# MCU.net
KiCad netlist of a schematic drawn in Altium Designer
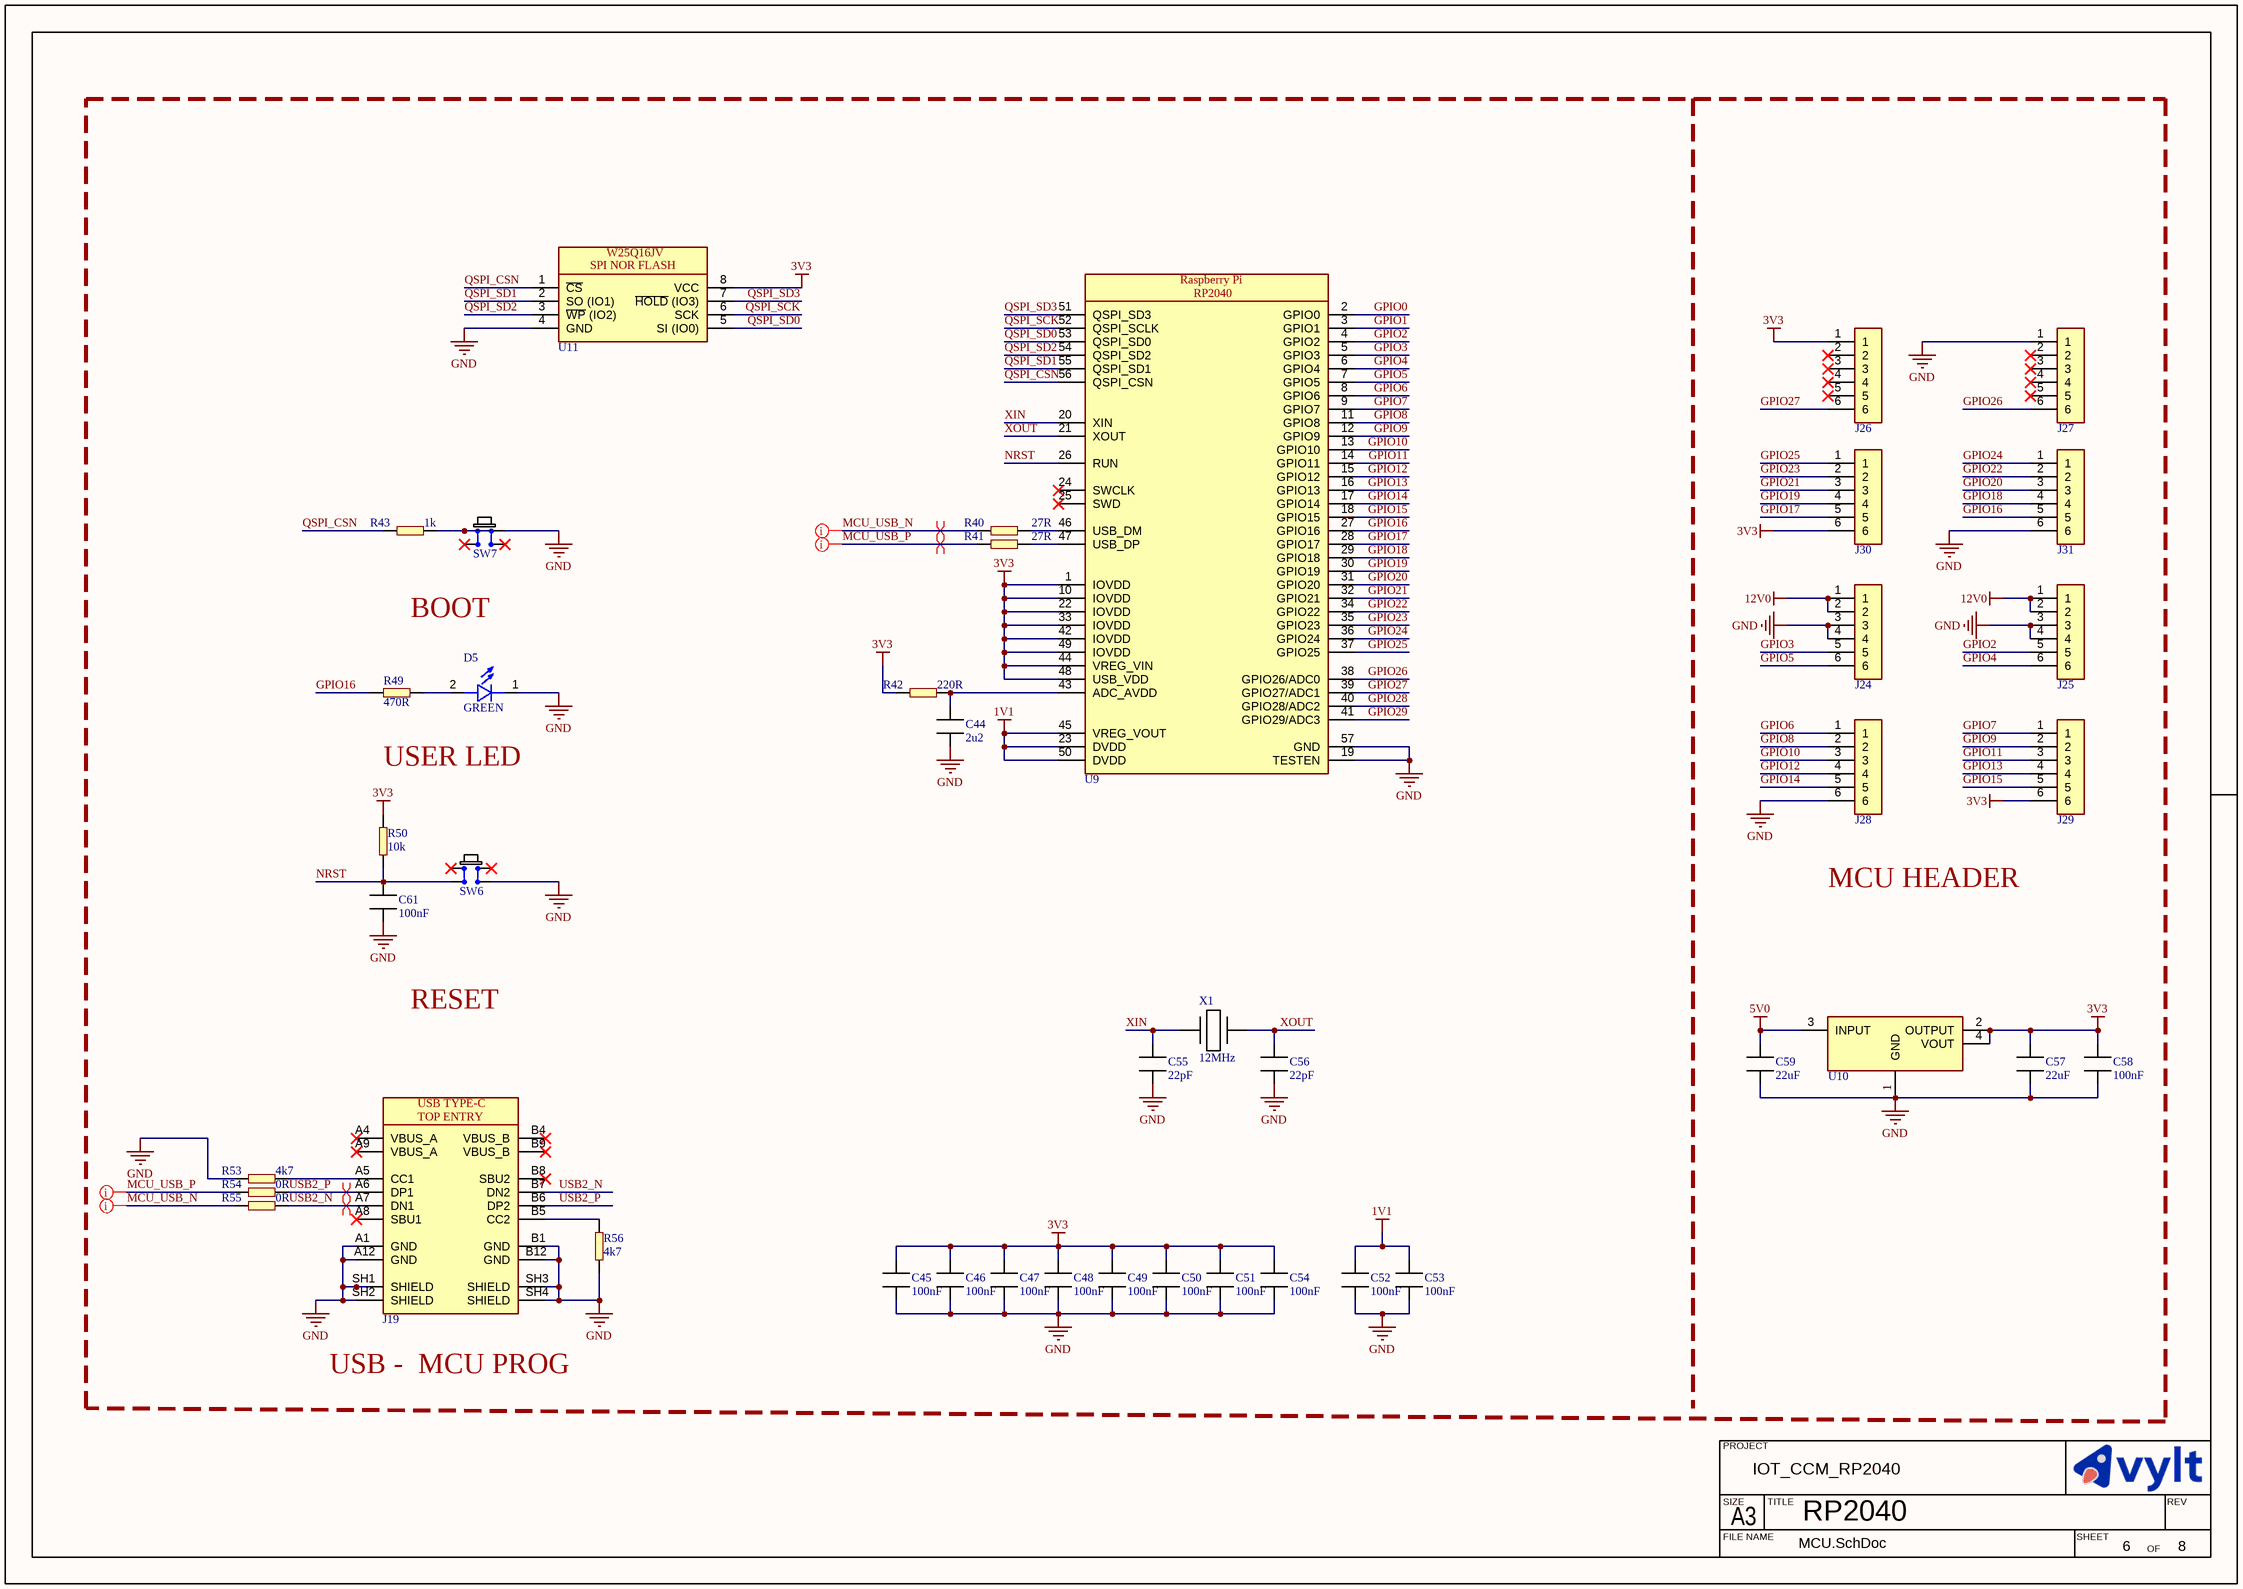
[diagram p0: MCU.SchDoc]

(export (version "E")
  (design (tool "Eeschema 10.0.6"))
  (components
    (comp (ref "C44")
      (value "2u2")
      (footprint "CAPC2012X13L")
      (description "Chip Capacitor, 2-Leads, Body 2.00x1.25mm, IPC High Density")
      (fields (field (name "Comment") "MLCC_0805"))
      (libsource (lib "Capacitor") (part "MLCC_0805"))
    )
    (comp (ref "C45")
      (value "100nF")
      (footprint "CAPC2012X13L")
      (description "Chip Capacitor, 2-Leads, Body 2.00x1.25mm, IPC High Density")
      (fields (field (name "Comment") "MLCC_0805"))
      (libsource (lib "Capacitor") (part "MLCC_0805"))
    )
    (comp (ref "C46")
      (value "100nF")
      (footprint "CAPC2012X13L")
      (description "Chip Capacitor, 2-Leads, Body 2.00x1.25mm, IPC High Density")
      (fields (field (name "Comment") "MLCC_0805"))
      (libsource (lib "Capacitor") (part "MLCC_0805"))
    )
    (comp (ref "C47")
      (value "100nF")
      (footprint "CAPC2012X13L")
      (description "Chip Capacitor, 2-Leads, Body 2.00x1.25mm, IPC High Density")
      (fields (field (name "Comment") "MLCC_0805"))
      (libsource (lib "Capacitor") (part "MLCC_0805"))
    )
    (comp (ref "C48")
      (value "100nF")
      (footprint "CAPC2012X13L")
      (description "Chip Capacitor, 2-Leads, Body 2.00x1.25mm, IPC High Density")
      (fields (field (name "Comment") "MLCC_0805"))
      (libsource (lib "Capacitor") (part "MLCC_0805"))
    )
    (comp (ref "C49")
      (value "100nF")
      (footprint "CAPC2012X13L")
      (description "Chip Capacitor, 2-Leads, Body 2.00x1.25mm, IPC High Density")
      (fields (field (name "Comment") "MLCC_0805"))
      (libsource (lib "Capacitor") (part "MLCC_0805"))
    )
    (comp (ref "C50")
      (value "100nF")
      (footprint "CAPC2012X13L")
      (description "Chip Capacitor, 2-Leads, Body 2.00x1.25mm, IPC High Density")
      (fields (field (name "Comment") "MLCC_0805"))
      (libsource (lib "Capacitor") (part "MLCC_0805"))
    )
    (comp (ref "C51")
      (value "100nF")
      (footprint "CAPC2012X13L")
      (description "Chip Capacitor, 2-Leads, Body 2.00x1.25mm, IPC High Density")
      (fields (field (name "Comment") "MLCC_0805"))
      (libsource (lib "Capacitor") (part "MLCC_0805"))
    )
    (comp (ref "C52")
      (value "100nF")
      (footprint "CAPC2012X13L")
      (description "Chip Capacitor, 2-Leads, Body 2.00x1.25mm, IPC High Density")
      (fields (field (name "Comment") "MLCC_0805"))
      (libsource (lib "Capacitor") (part "MLCC_0805"))
    )
    (comp (ref "C53")
      (value "100nF")
      (footprint "CAPC2012X13L")
      (description "Chip Capacitor, 2-Leads, Body 2.00x1.25mm, IPC High Density")
      (fields (field (name "Comment") "MLCC_0805"))
      (libsource (lib "Capacitor") (part "MLCC_0805"))
    )
    (comp (ref "C54")
      (value "100nF")
      (footprint "CAPC2012X13L")
      (description "Chip Capacitor, 2-Leads, Body 2.00x1.25mm, IPC High Density")
      (fields (field (name "Comment") "MLCC_0805"))
      (libsource (lib "Capacitor") (part "MLCC_0805"))
    )
    (comp (ref "C55")
      (value "22pF")
      (footprint "CAPC2012X13L")
      (description "Chip Capacitor, 2-Leads, Body 2.00x1.25mm, IPC High Density")
      (fields (field (name "Comment") "MLCC_0805"))
      (libsource (lib "Capacitor") (part "MLCC_0805"))
    )
    (comp (ref "C56")
      (value "22pF")
      (footprint "CAPC2012X13L")
      (description "Chip Capacitor, 2-Leads, Body 2.00x1.25mm, IPC High Density")
      (fields (field (name "Comment") "MLCC_0805"))
      (libsource (lib "Capacitor") (part "MLCC_0805"))
    )
    (comp (ref "C57")
      (value "22uF")
      (footprint "CAPC2012X13L")
      (description "Chip Capacitor, 2-Leads, Body 2.00x1.25mm, IPC High Density")
      (fields (field (name "Comment") "MLCC_0805"))
      (libsource (lib "Capacitor") (part "MLCC_0805"))
    )
    (comp (ref "C58")
      (value "100nF")
      (footprint "CAPC2012X13L")
      (description "Chip Capacitor, 2-Leads, Body 2.00x1.25mm, IPC High Density")
      (fields (field (name "Comment") "MLCC_0805"))
      (libsource (lib "Capacitor") (part "MLCC_0805"))
    )
    (comp (ref "C59")
      (value "22uF")
      (footprint "CAPC2012X13L")
      (description "Chip Capacitor, 2-Leads, Body 2.00x1.25mm, IPC High Density")
      (fields (field (name "Comment") "MLCC_0805"))
      (libsource (lib "Capacitor") (part "MLCC_0805"))
    )
    (comp (ref "C61")
      (value "100nF")
      (footprint "CAPC2012X13L")
      (description "Chip Capacitor, 2-Leads, Body 2.00x1.25mm, IPC High Density")
      (fields (field (name "Comment") "MLCC_0805"))
      (libsource (lib "Capacitor") (part "MLCC_0805"))
    )
    (comp (ref "D5")
      (value "GREEN")
      (footprint "LED_1206")
      (description "LED CLEAR 1206 SMD")
      (fields (field (name "Comment") "LED_1206"))
      (libsource (lib "LED") (part "LED_1206"))
    )
    (comp (ref "J19")
      (value "GSB1CA11101DSHR")
      (footprint "GSB1CA11101DSHR")
      (libsource (lib "Connectors") (part "GSB1CA11101DSHR"))
    )
    (comp (ref "J24")
      (value "ERP_148-2")
      (footprint "6PX1R_F")
      (description "6PX1R Female Header")
      (libsource (lib "PinHeader") (part "6PX1R_F"))
    )
    (comp (ref "J25")
      (value "ERP_148-2")
      (footprint "6PX1R_F")
      (description "6PX1R Female Header")
      (libsource (lib "PinHeader") (part "6PX1R_F"))
    )
    (comp (ref "J26")
      (value "ERP_148-2")
      (footprint "6PX1R_F")
      (description "6PX1R Female Header")
      (libsource (lib "PinHeader") (part "6PX1R_F"))
    )
    (comp (ref "J27")
      (value "ERP_148-2")
      (footprint "6PX1R_F")
      (description "6PX1R Female Header")
      (libsource (lib "PinHeader") (part "6PX1R_F"))
    )
    (comp (ref "J28")
      (value "ERP_148-2")
      (footprint "6PX1R_F")
      (description "6PX1R Female Header")
      (libsource (lib "PinHeader") (part "6PX1R_F"))
    )
    (comp (ref "J29")
      (value "ERP_148-2")
      (footprint "6PX1R_F")
      (description "6PX1R Female Header")
      (libsource (lib "PinHeader") (part "6PX1R_F"))
    )
    (comp (ref "J30")
      (value "ERP_148-2")
      (footprint "6PX1R_F")
      (description "6PX1R Female Header")
      (libsource (lib "PinHeader") (part "6PX1R_F"))
    )
    (comp (ref "J31")
      (value "ERP_148-2")
      (footprint "6PX1R_F")
      (description "6PX1R Female Header")
      (libsource (lib "PinHeader") (part "6PX1R_F"))
    )
    (comp (ref "R40")
      (value "27R")
      (footprint "RES_0603")
      (description "RES_0603")
      (fields (field (name "Comment") "ERP_101-1"))
      (libsource (lib "") (part "RES_0603_1"))
    )
    (comp (ref "R41")
      (value "27R")
      (footprint "RES_0603")
      (description "RES_0603")
      (fields (field (name "Comment") "ERP_101-1"))
      (libsource (lib "") (part "RES_0603_1"))
    )
    (comp (ref "R42")
      (value "220R")
      (footprint "RES_0603")
      (description "RES_0603")
      (fields (field (name "Comment") "ERP_101-1"))
      (libsource (lib "") (part "RES_0603_1"))
    )
    (comp (ref "R43")
      (value "1k")
      (footprint "RES_0603")
      (description "RES_0603")
      (fields (field (name "Comment") "ERP_101-1"))
      (libsource (lib "") (part "RES_0603_1"))
    )
    (comp (ref "R49")
      (value "470R")
      (footprint "RES_0603")
      (description "RES_0603")
      (fields (field (name "Comment") "ERP_101-1"))
      (libsource (lib "") (part "RES_0603_1"))
    )
    (comp (ref "R50")
      (value "10k")
      (footprint "RES_0603")
      (description "RES_0603")
      (fields (field (name "Comment") "ERP_101-1"))
      (libsource (lib "Resistor") (part "RES_0603"))
    )
    (comp (ref "R53")
      (value "4k7")
      (footprint "RES_0603")
      (description "RES_0603")
      (fields (field (name "Comment") "ERP_101-1"))
      (libsource (lib "") (part "RES_0603_1"))
    )
    (comp (ref "R54")
      (value "0R")
      (footprint "RES_0603")
      (description "RES_0603")
      (fields (field (name "Comment") "ERP_101-1"))
      (libsource (lib "") (part "RES_0603_1"))
    )
    (comp (ref "R55")
      (value "0R")
      (footprint "RES_0603")
      (description "RES_0603")
      (fields (field (name "Comment") "ERP_101-1"))
      (libsource (lib "") (part "RES_0603_1"))
    )
    (comp (ref "R56")
      (value "4k7")
      (footprint "RES_0603")
      (description "RES_0603")
      (fields (field (name "Comment") "ERP_101-1"))
      (libsource (lib "") (part "RES_0603_2"))
    )
    (comp (ref "SW6")
      (value "Generic6X6")
      (footprint "Generic6X6")
      (description "Tactile Switch SPST-NO Top Actuated Surface Mount")
      (libsource (lib "Switch") (part "Generic6X6"))
    )
    (comp (ref "SW7")
      (value "Generic6X6")
      (footprint "Generic6X6")
      (description "Tactile Switch SPST-NO Top Actuated Surface Mount")
      (libsource (lib "Switch") (part "Generic6X6"))
    )
    (comp (ref "U9")
      (value "RP2040")
      (footprint "QFN40P700X700X90-57N")
      (description "ARM® Cortex®-M0+ - Microcontroller IC 32-Bit Dual-Core 133MHz External Program Memory 56-QFN (7x7)")
      (libsource (lib "MCU") (part "RP2040"))
    )
    (comp (ref "U10")
      (value "ERP_123-1")
      (footprint "AMS1117_SOT223")
      (description "AMS1117 LDO")
      (libsource (lib "VoltageRegulator") (part "AMS1117_SOT223"))
    )
    (comp (ref "U11")
      (value "W25Q16JV")
      (footprint "SOIC127P600X175-8M")
      (description "FLASH - NOR Memory IC SPI - Quad I/O 133 MHz 8-SOIC")
      (libsource (lib "FLASH") (part "W25Q16JV"))
    )
    (comp (ref "X1")
      (value "12MHz")
      (footprint "X5032")
      (description "CRYSTAL X5032 2 Pin")
      (fields (field (name "Comment") "X5032"))
      (libsource (lib "Crystal") (part "X5032"))
    )
  )
  (nets
    (net (code "1") (name "/GPIO0") (class "Default")
      (node (ref "U9") (pin "2") (pinfunction "GPIO0_2") (pintype "passive"))
    )
    (net (code "2") (name "/GPIO1") (class "Default")
      (node (ref "U9") (pin "3") (pinfunction "GPIO1_3") (pintype "passive"))
    )
    (net (code "3") (name "/GPIO2") (class "Default")
      (node (ref "J25") (pin "5") (pinfunction "5_5") (pintype "passive"))
      (node (ref "U9") (pin "4") (pinfunction "GPIO2_4") (pintype "passive"))
    )
    (net (code "4") (name "/GPIO3") (class "Default")
      (node (ref "J24") (pin "5") (pinfunction "5_5") (pintype "passive"))
      (node (ref "U9") (pin "5") (pinfunction "GPIO3_5") (pintype "passive"))
    )
    (net (code "5") (name "/GPIO4") (class "Default")
      (node (ref "J25") (pin "6") (pinfunction "6_6") (pintype "passive"))
      (node (ref "U9") (pin "6") (pinfunction "GPIO4_6") (pintype "passive"))
    )
    (net (code "6") (name "/GPIO5") (class "Default")
      (node (ref "J24") (pin "6") (pinfunction "6_6") (pintype "passive"))
      (node (ref "U9") (pin "7") (pinfunction "GPIO5_7") (pintype "passive"))
    )
    (net (code "7") (name "/GPIO6") (class "Default")
      (node (ref "J28") (pin "1") (pinfunction "1_1") (pintype "passive"))
      (node (ref "U9") (pin "8") (pinfunction "GPIO6_8") (pintype "passive"))
    )
    (net (code "8") (name "/GPIO7") (class "Default")
      (node (ref "J29") (pin "1") (pinfunction "1_1") (pintype "passive"))
      (node (ref "U9") (pin "9") (pinfunction "GPIO7_9") (pintype "passive"))
    )
    (net (code "9") (name "/GPIO8") (class "Default")
      (node (ref "J28") (pin "2") (pinfunction "2_2") (pintype "passive"))
      (node (ref "U9") (pin "11") (pinfunction "GPIO8_11") (pintype "passive"))
    )
    (net (code "10") (name "/GPIO9") (class "Default")
      (node (ref "J29") (pin "2") (pinfunction "2_2") (pintype "passive"))
      (node (ref "U9") (pin "12") (pinfunction "GPIO9_12") (pintype "passive"))
    )
    (net (code "11") (name "/GPIO10") (class "Default")
      (node (ref "J28") (pin "3") (pinfunction "3_3") (pintype "passive"))
      (node (ref "U9") (pin "13") (pinfunction "GPIO10_13") (pintype "passive"))
    )
    (net (code "12") (name "/GPIO11") (class "Default")
      (node (ref "J29") (pin "3") (pinfunction "3_3") (pintype "passive"))
      (node (ref "U9") (pin "14") (pinfunction "GPIO11_14") (pintype "passive"))
    )
    (net (code "13") (name "/GPIO12") (class "Default")
      (node (ref "J28") (pin "4") (pinfunction "4_4") (pintype "passive"))
      (node (ref "U9") (pin "15") (pinfunction "GPIO12_15") (pintype "passive"))
    )
    (net (code "14") (name "/GPIO13") (class "Default")
      (node (ref "J29") (pin "4") (pinfunction "4_4") (pintype "passive"))
      (node (ref "U9") (pin "16") (pinfunction "GPIO13_16") (pintype "passive"))
    )
    (net (code "15") (name "/GPIO14") (class "Default")
      (node (ref "J28") (pin "5") (pinfunction "5_5") (pintype "passive"))
      (node (ref "U9") (pin "17") (pinfunction "GPIO14_17") (pintype "passive"))
    )
    (net (code "16") (name "/GPIO15") (class "Default")
      (node (ref "J29") (pin "5") (pinfunction "5_5") (pintype "passive"))
      (node (ref "U9") (pin "18") (pinfunction "GPIO15_18") (pintype "passive"))
    )
    (net (code "17") (name "/GPIO16") (class "Default")
      (node (ref "J31") (pin "5") (pinfunction "5_5") (pintype "passive"))
      (node (ref "R49") (pin "2") (pinfunction "2_2") (pintype "passive"))
      (node (ref "U9") (pin "27") (pinfunction "GPIO16_27") (pintype "passive"))
    )
    (net (code "18") (name "/GPIO17") (class "Default")
      (node (ref "J30") (pin "5") (pinfunction "5_5") (pintype "passive"))
      (node (ref "U9") (pin "28") (pinfunction "GPIO17_28") (pintype "passive"))
    )
    (net (code "19") (name "/GPIO18") (class "Default")
      (node (ref "J31") (pin "4") (pinfunction "4_4") (pintype "passive"))
      (node (ref "U9") (pin "29") (pinfunction "GPIO18_29") (pintype "passive"))
    )
    (net (code "20") (name "/GPIO19") (class "Default")
      (node (ref "J30") (pin "4") (pinfunction "4_4") (pintype "passive"))
      (node (ref "U9") (pin "30") (pinfunction "GPIO19_30") (pintype "passive"))
    )
    (net (code "21") (name "/GPIO20") (class "Default")
      (node (ref "J31") (pin "3") (pinfunction "3_3") (pintype "passive"))
      (node (ref "U9") (pin "31") (pinfunction "GPIO20_31") (pintype "passive"))
    )
    (net (code "22") (name "/GPIO21") (class "Default")
      (node (ref "J30") (pin "3") (pinfunction "3_3") (pintype "passive"))
      (node (ref "U9") (pin "32") (pinfunction "GPIO21_32") (pintype "passive"))
    )
    (net (code "23") (name "/GPIO22") (class "Default")
      (node (ref "J31") (pin "2") (pinfunction "2_2") (pintype "passive"))
      (node (ref "U9") (pin "34") (pinfunction "GPIO22_34") (pintype "passive"))
    )
    (net (code "24") (name "/GPIO23") (class "Default")
      (node (ref "J30") (pin "2") (pinfunction "2_2") (pintype "passive"))
      (node (ref "U9") (pin "35") (pinfunction "GPIO23_35") (pintype "passive"))
    )
    (net (code "25") (name "/GPIO24") (class "Default")
      (node (ref "J31") (pin "1") (pinfunction "1_1") (pintype "passive"))
      (node (ref "U9") (pin "36") (pinfunction "GPIO24_36") (pintype "passive"))
    )
    (net (code "26") (name "/GPIO25") (class "Default")
      (node (ref "J30") (pin "1") (pinfunction "1_1") (pintype "passive"))
      (node (ref "U9") (pin "37") (pinfunction "GPIO25_37") (pintype "passive"))
    )
    (net (code "27") (name "/GPIO26") (class "Default")
      (node (ref "J27") (pin "6") (pinfunction "6_6") (pintype "passive"))
      (node (ref "U9") (pin "38") (pinfunction "GPIO26/ADC0_38") (pintype "passive"))
    )
    (net (code "28") (name "/GPIO27") (class "Default")
      (node (ref "J26") (pin "6") (pinfunction "6_6") (pintype "passive"))
      (node (ref "U9") (pin "39") (pinfunction "GPIO27/ADC1_39") (pintype "passive"))
    )
    (net (code "29") (name "/GPIO28") (class "Default")
      (node (ref "U9") (pin "40") (pinfunction "GPIO28/ADC2_40") (pintype "passive"))
    )
    (net (code "30") (name "/GPIO29") (class "Default")
      (node (ref "U9") (pin "41") (pinfunction "GPIO29/ADC3_41") (pintype "passive"))
    )
    (net (code "31") (name "/MCU_USB_N") (class "Default")
      (node (ref "R40") (pin "2") (pinfunction "2_2") (pintype "passive"))
      (node (ref "R55") (pin "2") (pinfunction "2_2") (pintype "passive"))
    )
    (net (code "32") (name "/MCU_USB_P") (class "Default")
      (node (ref "R41") (pin "2") (pinfunction "2_2") (pintype "passive"))
      (node (ref "R54") (pin "2") (pinfunction "2_2") (pintype "passive"))
    )
    (net (code "33") (name "/NRST") (class "Default")
      (node (ref "C61") (pin "1") (pinfunction "1_1") (pintype "passive"))
      (node (ref "R50") (pin "1") (pinfunction "1_1") (pintype "passive"))
      (node (ref "SW6") (pin "2") (pinfunction "NO_2") (pintype "passive"))
      (node (ref "U9") (pin "26") (pinfunction "RUN_26") (pintype "passive"))
    )
    (net (code "34") (name "/QSPI_CSN") (class "Default")
      (node (ref "R43") (pin "2") (pinfunction "2_2") (pintype "passive"))
      (node (ref "U11") (pin "1") (pinfunction "~{CS}_1") (pintype "passive"))
      (node (ref "U9") (pin "56") (pinfunction "QSPI_CSN_56") (pintype "passive"))
    )
    (net (code "35") (name "/QSPI_SCK") (class "Default")
      (node (ref "U11") (pin "6") (pinfunction "SCK_6") (pintype "passive"))
      (node (ref "U9") (pin "52") (pinfunction "QSPI_SCLK_52") (pintype "passive"))
    )
    (net (code "36") (name "/QSPI_SD0") (class "Default")
      (node (ref "U11") (pin "5") (pinfunction "SI_(IO0)_5") (pintype "passive"))
      (node (ref "U9") (pin "53") (pinfunction "QSPI_SD0_53") (pintype "passive"))
    )
    (net (code "37") (name "/QSPI_SD1") (class "Default")
      (node (ref "U11") (pin "2") (pinfunction "SO_(IO1)_2") (pintype "passive"))
      (node (ref "U9") (pin "55") (pinfunction "QSPI_SD1_55") (pintype "passive"))
    )
    (net (code "38") (name "/QSPI_SD2") (class "Default")
      (node (ref "U11") (pin "3") (pinfunction "~{WP}_(IO2)_3") (pintype "passive"))
      (node (ref "U9") (pin "54") (pinfunction "QSPI_SD2_54") (pintype "passive"))
    )
    (net (code "39") (name "/QSPI_SD3") (class "Default")
      (node (ref "U11") (pin "7") (pinfunction "~{HOLD}_(IO3)_7") (pintype "passive"))
      (node (ref "U9") (pin "51") (pinfunction "QSPI_SD3_51") (pintype "passive"))
    )
    (net (code "40") (name "/USB2_N") (class "Default")
      (node (ref "J19") (pin "A7") (pinfunction "DN1_A7") (pintype "passive"))
      (node (ref "J19") (pin "B7") (pinfunction "DN2_B7") (pintype "passive"))
      (node (ref "R55") (pin "1") (pinfunction "1_1") (pintype "passive"))
    )
    (net (code "41") (name "/USB2_P") (class "Default")
      (node (ref "J19") (pin "A6") (pinfunction "DP1_A6") (pintype "passive"))
      (node (ref "J19") (pin "B6") (pinfunction "DP2_B6") (pintype "passive"))
      (node (ref "R54") (pin "1") (pinfunction "1_1") (pintype "passive"))
    )
    (net (code "42") (name "/XIN") (class "Default")
      (node (ref "C55") (pin "1") (pinfunction "1_1") (pintype "passive"))
      (node (ref "U9") (pin "20") (pinfunction "XIN_20") (pintype "passive"))
      (node (ref "X1") (pin "1") (pinfunction "1_1") (pintype "passive"))
    )
    (net (code "43") (name "/XOUT") (class "Default")
      (node (ref "C56") (pin "1") (pinfunction "1_1") (pintype "passive"))
      (node (ref "U9") (pin "21") (pinfunction "XOUT_21") (pintype "passive"))
      (node (ref "X1") (pin "2") (pinfunction "2_2") (pintype "passive"))
    )
    (net (code "44") (name "1V1") (class "Default")
      (node (ref "C52") (pin "1") (pinfunction "1_1") (pintype "passive"))
      (node (ref "C53") (pin "1") (pinfunction "1_1") (pintype "passive"))
      (node (ref "U9") (pin "23") (pinfunction "DVDD_23") (pintype "passive"))
      (node (ref "U9") (pin "45") (pinfunction "VREG_VOUT_45") (pintype "passive"))
      (node (ref "U9") (pin "50") (pinfunction "DVDD_50") (pintype "passive"))
    )
    (net (code "45") (name "3V3") (class "Default")
      (node (ref "C45") (pin "1") (pinfunction "1_1") (pintype "passive"))
      (node (ref "C46") (pin "1") (pinfunction "1_1") (pintype "passive"))
      (node (ref "C47") (pin "1") (pinfunction "1_1") (pintype "passive"))
      (node (ref "C48") (pin "1") (pinfunction "1_1") (pintype "passive"))
      (node (ref "C49") (pin "1") (pinfunction "1_1") (pintype "passive"))
      (node (ref "C50") (pin "1") (pinfunction "1_1") (pintype "passive"))
      (node (ref "C51") (pin "1") (pinfunction "1_1") (pintype "passive"))
      (node (ref "C54") (pin "1") (pinfunction "1_1") (pintype "passive"))
      (node (ref "C57") (pin "1") (pinfunction "1_1") (pintype "passive"))
      (node (ref "C58") (pin "1") (pinfunction "1_1") (pintype "passive"))
      (node (ref "J26") (pin "1") (pinfunction "1_1") (pintype "passive"))
      (node (ref "J29") (pin "6") (pinfunction "6_6") (pintype "passive"))
      (node (ref "J30") (pin "6") (pinfunction "6_6") (pintype "passive"))
      (node (ref "R42") (pin "2") (pinfunction "2_2") (pintype "passive"))
      (node (ref "R50") (pin "2") (pinfunction "2_2") (pintype "passive"))
      (node (ref "U10") (pin "2") (pinfunction "OUTPUT_2") (pintype "passive"))
      (node (ref "U10") (pin "4") (pinfunction "VOUT_4") (pintype "passive"))
      (node (ref "U11") (pin "8") (pinfunction "VCC_8") (pintype "passive"))
      (node (ref "U9") (pin "1") (pinfunction "IOVDD_1") (pintype "passive"))
      (node (ref "U9") (pin "10") (pinfunction "IOVDD_10") (pintype "passive"))
      (node (ref "U9") (pin "22") (pinfunction "IOVDD_22") (pintype "passive"))
      (node (ref "U9") (pin "33") (pinfunction "IOVDD_33") (pintype "passive"))
      (node (ref "U9") (pin "42") (pinfunction "IOVDD_42") (pintype "passive"))
      (node (ref "U9") (pin "44") (pinfunction "VREG_VIN_44") (pintype "passive"))
      (node (ref "U9") (pin "48") (pinfunction "USB_VDD_48") (pintype "passive"))
      (node (ref "U9") (pin "49") (pinfunction "IOVDD_49") (pintype "passive"))
    )
    (net (code "46") (name "5V0") (class "Default")
      (node (ref "C59") (pin "1") (pinfunction "1_1") (pintype "passive"))
      (node (ref "U10") (pin "3") (pinfunction "INPUT_3") (pintype "passive"))
    )
    (net (code "47") (name "12V0") (class "Default")
      (node (ref "J24") (pin "1") (pinfunction "1_1") (pintype "passive"))
      (node (ref "J24") (pin "2") (pinfunction "2_2") (pintype "passive"))
      (node (ref "J25") (pin "1") (pinfunction "1_1") (pintype "passive"))
      (node (ref "J25") (pin "2") (pinfunction "2_2") (pintype "passive"))
    )
    (net (code "48") (name "GND") (class "Default")
      (node (ref "C44") (pin "2") (pinfunction "2_2") (pintype "passive"))
      (node (ref "C45") (pin "2") (pinfunction "2_2") (pintype "passive"))
      (node (ref "C46") (pin "2") (pinfunction "2_2") (pintype "passive"))
      (node (ref "C47") (pin "2") (pinfunction "2_2") (pintype "passive"))
      (node (ref "C48") (pin "2") (pinfunction "2_2") (pintype "passive"))
      (node (ref "C49") (pin "2") (pinfunction "2_2") (pintype "passive"))
      (node (ref "C50") (pin "2") (pinfunction "2_2") (pintype "passive"))
      (node (ref "C51") (pin "2") (pinfunction "2_2") (pintype "passive"))
      (node (ref "C52") (pin "2") (pinfunction "2_2") (pintype "passive"))
      (node (ref "C53") (pin "2") (pinfunction "2_2") (pintype "passive"))
      (node (ref "C54") (pin "2") (pinfunction "2_2") (pintype "passive"))
      (node (ref "C55") (pin "2") (pinfunction "2_2") (pintype "passive"))
      (node (ref "C56") (pin "2") (pinfunction "2_2") (pintype "passive"))
      (node (ref "C57") (pin "2") (pinfunction "2_2") (pintype "passive"))
      (node (ref "C58") (pin "2") (pinfunction "2_2") (pintype "passive"))
      (node (ref "C59") (pin "2") (pinfunction "2_2") (pintype "passive"))
      (node (ref "C61") (pin "2") (pinfunction "2_2") (pintype "passive"))
      (node (ref "D5") (pin "1") (pinfunction "1_1") (pintype "passive"))
      (node (ref "J19") (pin "A1") (pinfunction "GND_A1") (pintype "power_in"))
      (node (ref "J19") (pin "A12") (pinfunction "GND_A12") (pintype "power_in"))
      (node (ref "J19") (pin "B1") (pinfunction "GND_B1") (pintype "power_in"))
      (node (ref "J19") (pin "B12") (pinfunction "GND_B12") (pintype "power_in"))
      (node (ref "J19") (pin "SH1") (pinfunction "SHIELD_SH1") (pintype "passive"))
      (node (ref "J19") (pin "SH2") (pinfunction "SHIELD_SH2") (pintype "passive"))
      (node (ref "J19") (pin "SH3") (pinfunction "SHIELD_SH3") (pintype "passive"))
      (node (ref "J19") (pin "SH4") (pinfunction "SHIELD_SH4") (pintype "passive"))
      (node (ref "J24") (pin "3") (pinfunction "3_3") (pintype "passive"))
      (node (ref "J24") (pin "4") (pinfunction "4_4") (pintype "passive"))
      (node (ref "J25") (pin "3") (pinfunction "3_3") (pintype "passive"))
      (node (ref "J25") (pin "4") (pinfunction "4_4") (pintype "passive"))
      (node (ref "J27") (pin "1") (pinfunction "1_1") (pintype "passive"))
      (node (ref "J28") (pin "6") (pinfunction "6_6") (pintype "passive"))
      (node (ref "J31") (pin "6") (pinfunction "6_6") (pintype "passive"))
      (node (ref "R53") (pin "2") (pinfunction "2_2") (pintype "passive"))
      (node (ref "R56") (pin "2") (pinfunction "2_2") (pintype "passive"))
      (node (ref "SW6") (pin "4") (pinfunction "COM_4") (pintype "passive"))
      (node (ref "SW7") (pin "1") (pinfunction "NO_1") (pintype "passive"))
      (node (ref "U10") (pin "1") (pinfunction "GND_1") (pintype "power_in"))
      (node (ref "U11") (pin "4") (pinfunction "GND_4") (pintype "passive"))
      (node (ref "U9") (pin "19") (pinfunction "TESTEN_19") (pintype "passive"))
      (node (ref "U9") (pin "57") (pinfunction "GND_57") (pintype "passive"))
    )
    (net (code "49") (name "Net-(D5-Pad2)") (class "Default")
      (node (ref "D5") (pin "2") (pinfunction "2_2") (pintype "passive"))
      (node (ref "R49") (pin "1") (pinfunction "1_1") (pintype "passive"))
    )
    (net (code "50") (name "Net-(J19-CC1)") (class "Default")
      (node (ref "J19") (pin "A5") (pinfunction "CC1_A5") (pintype "passive"))
      (node (ref "R53") (pin "1") (pinfunction "1_1") (pintype "passive"))
    )
    (net (code "51") (name "Net-(J19-CC2)") (class "Default")
      (node (ref "J19") (pin "B5") (pinfunction "CC2_B5") (pintype "passive"))
      (node (ref "R56") (pin "1") (pinfunction "1_1") (pintype "passive"))
    )
    (net (code "52") (name "Net-(R43-Pad1)") (class "Default")
      (node (ref "R43") (pin "1") (pinfunction "1_1") (pintype "passive"))
      (node (ref "SW7") (pin "3") (pinfunction "COM_3") (pintype "passive"))
    )
    (net (code "53") (name "Net-(U9-ADC_AVDD)") (class "Default")
      (node (ref "C44") (pin "1") (pinfunction "1_1") (pintype "passive"))
      (node (ref "R42") (pin "1") (pinfunction "1_1") (pintype "passive"))
      (node (ref "U9") (pin "43") (pinfunction "ADC_AVDD_43") (pintype "passive"))
    )
    (net (code "54") (name "Net-(U9-USB_DM)") (class "Default")
      (node (ref "R40") (pin "1") (pinfunction "1_1") (pintype "passive"))
      (node (ref "U9") (pin "46") (pinfunction "USB_DM_46") (pintype "passive"))
    )
    (net (code "55") (name "Net-(U9-USB_DP)") (class "Default")
      (node (ref "R41") (pin "1") (pinfunction "1_1") (pintype "passive"))
      (node (ref "U9") (pin "47") (pinfunction "USB_DP_47") (pintype "passive"))
    )
    (net (code "56") (name "unconnected-(J19-SBU1-PadA8)") (class "Default")
      (node (ref "J19") (pin "A8") (pinfunction "SBU1_A8") (pintype "passive+no_connect"))
    )
    (net (code "57") (name "unconnected-(J19-SBU2-PadB8)") (class "Default")
      (node (ref "J19") (pin "B8") (pinfunction "SBU2_B8") (pintype "passive+no_connect"))
    )
    (net (code "58") (name "unconnected-(J19-VBUS_A-PadA4)") (class "Default")
      (node (ref "J19") (pin "A4") (pinfunction "VBUS_A_A4") (pintype "power_in+no_connect"))
    )
    (net (code "59") (name "unconnected-(J19-VBUS_A-PadA9)") (class "Default")
      (node (ref "J19") (pin "A9") (pinfunction "VBUS_A_A9") (pintype "power_in+no_connect"))
    )
    (net (code "60") (name "unconnected-(J19-VBUS_B-PadB4)") (class "Default")
      (node (ref "J19") (pin "B4") (pinfunction "VBUS_B_B4") (pintype "power_in+no_connect"))
    )
    (net (code "61") (name "unconnected-(J19-VBUS_B-PadB9)") (class "Default")
      (node (ref "J19") (pin "B9") (pinfunction "VBUS_B_B9") (pintype "power_in+no_connect"))
    )
    (net (code "62") (name "unconnected-(J26-Pad2)") (class "Default")
      (node (ref "J26") (pin "2") (pinfunction "2_2") (pintype "passive+no_connect"))
    )
    (net (code "63") (name "unconnected-(J26-Pad3)") (class "Default")
      (node (ref "J26") (pin "3") (pinfunction "3_3") (pintype "passive+no_connect"))
    )
    (net (code "64") (name "unconnected-(J26-Pad4)") (class "Default")
      (node (ref "J26") (pin "4") (pinfunction "4_4") (pintype "passive+no_connect"))
    )
    (net (code "65") (name "unconnected-(J26-Pad5)") (class "Default")
      (node (ref "J26") (pin "5") (pinfunction "5_5") (pintype "passive+no_connect"))
    )
    (net (code "66") (name "unconnected-(J27-Pad2)") (class "Default")
      (node (ref "J27") (pin "2") (pinfunction "2_2") (pintype "passive+no_connect"))
    )
    (net (code "67") (name "unconnected-(J27-Pad3)") (class "Default")
      (node (ref "J27") (pin "3") (pinfunction "3_3") (pintype "passive+no_connect"))
    )
    (net (code "68") (name "unconnected-(J27-Pad4)") (class "Default")
      (node (ref "J27") (pin "4") (pinfunction "4_4") (pintype "passive+no_connect"))
    )
    (net (code "69") (name "unconnected-(J27-Pad5)") (class "Default")
      (node (ref "J27") (pin "5") (pinfunction "5_5") (pintype "passive+no_connect"))
    )
    (net (code "70") (name "unconnected-(SW6-COM-Pad3)") (class "Default")
      (node (ref "SW6") (pin "3") (pinfunction "COM_3") (pintype "passive+no_connect"))
    )
    (net (code "71") (name "unconnected-(SW6-NO-Pad1)") (class "Default")
      (node (ref "SW6") (pin "1") (pinfunction "NO_1") (pintype "passive+no_connect"))
    )
    (net (code "72") (name "unconnected-(SW7-COM-Pad4)") (class "Default")
      (node (ref "SW7") (pin "4") (pinfunction "COM_4") (pintype "passive+no_connect"))
    )
    (net (code "73") (name "unconnected-(SW7-NO-Pad2)") (class "Default")
      (node (ref "SW7") (pin "2") (pinfunction "NO_2") (pintype "passive+no_connect"))
    )
    (net (code "74") (name "unconnected-(U9-SWCLK-Pad24)") (class "Default")
      (node (ref "U9") (pin "24") (pinfunction "SWCLK_24") (pintype "passive+no_connect"))
    )
    (net (code "75") (name "unconnected-(U9-SWD-Pad25)") (class "Default")
      (node (ref "U9") (pin "25") (pinfunction "SWD_25") (pintype "passive+no_connect"))
    )
  )
)
